# design.net
KiCad netlist of a schematic drawn in EasyEDA Pro
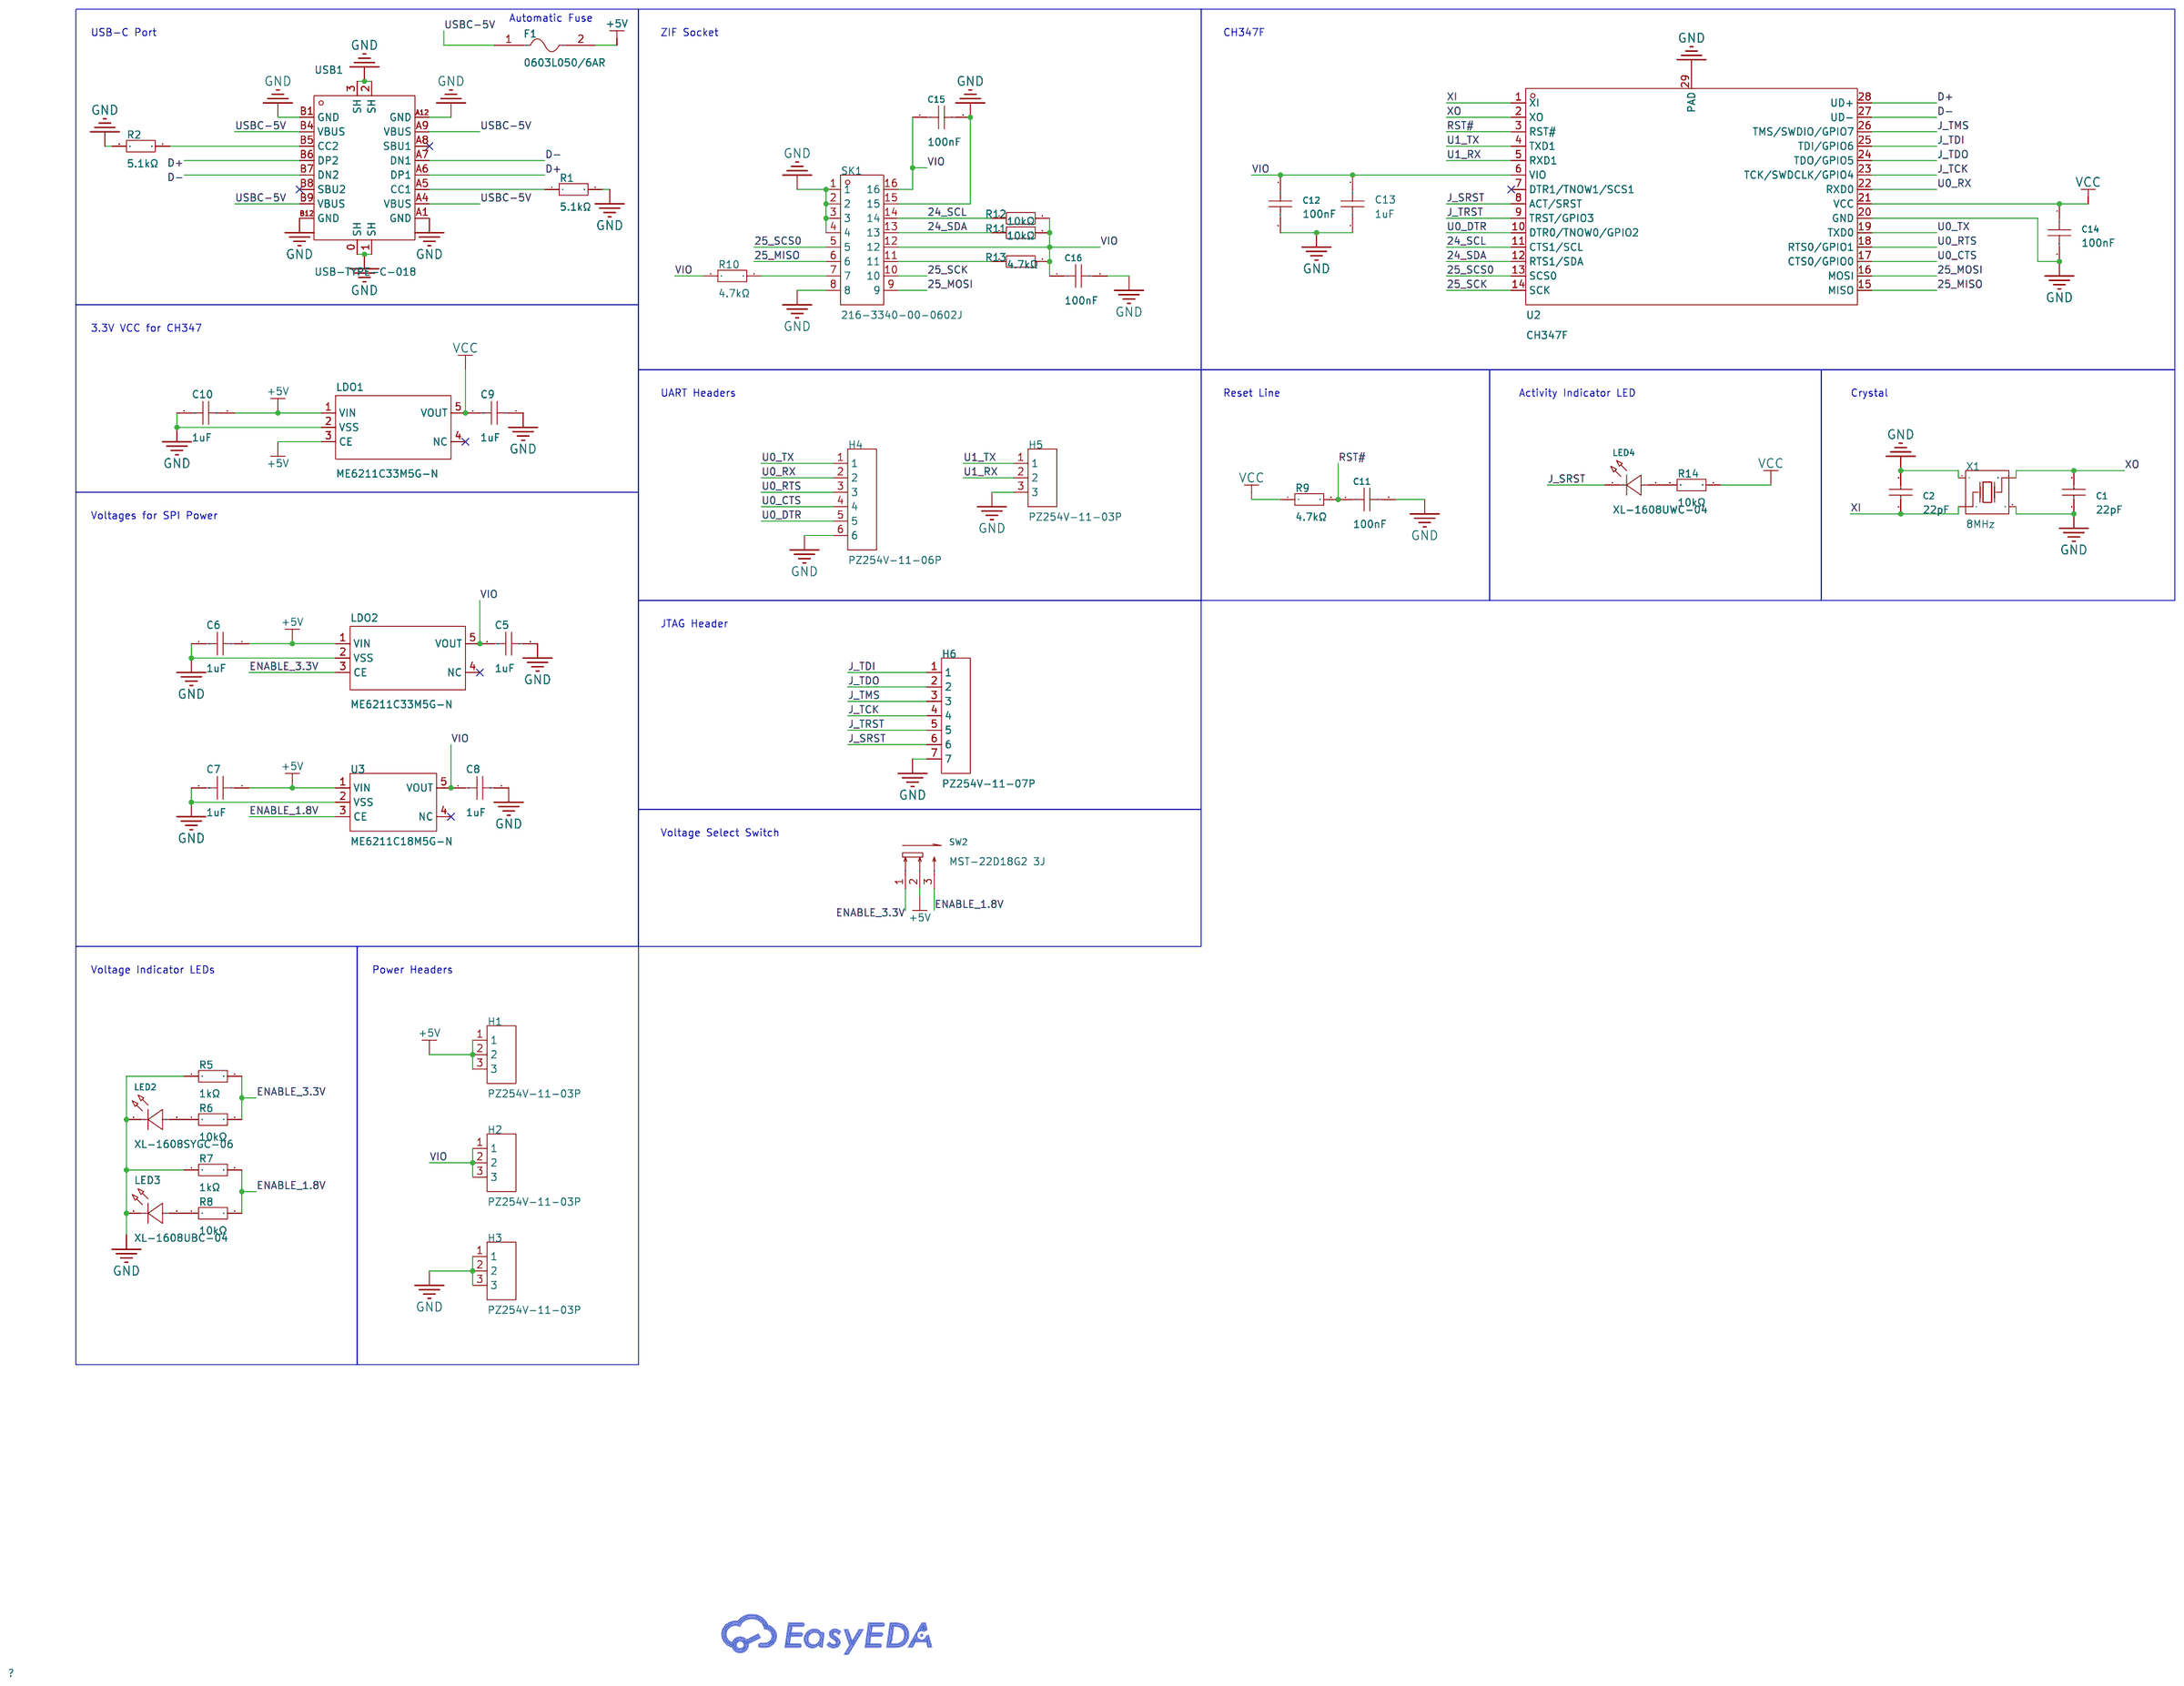
[diagram p0: schematic sheet]

(export (version "E")
  (design (tool "Eeschema 10.0.6"))
  (components
    (comp (ref "C1")
      (value "22pF")
      (footprint "easyedapro:C0402")
      (fields
        (field (name "Manufacturer Part") "CC0402JRNPO9BN220")
        (field (name "Manufacturer") "YAGEO(国巨)")
      )
      (libsource (lib "easyedapro") (part "CC0402JRNPO9BN220"))
    )
    (comp (ref "C2")
      (value "22pF")
      (footprint "easyedapro:C0402")
      (fields
        (field (name "Manufacturer Part") "CC0402JRNPO9BN220")
        (field (name "Manufacturer") "YAGEO(国巨)")
      )
      (libsource (lib "easyedapro") (part "CC0402JRNPO9BN220"))
    )
    (comp (ref "C5")
      (value "1uF")
      (footprint "easyedapro:C0603")
      (fields
        (field (name "Manufacturer Part") "CL10A105KB8NNNC")
        (field (name "Manufacturer") "SAMSUNG(三星)")
      )
      (libsource (lib "easyedapro") (part "CL10A105KB8NNNC"))
    )
    (comp (ref "C6")
      (value "1uF")
      (footprint "easyedapro:C0603")
      (fields
        (field (name "Manufacturer Part") "CL10A105KB8NNNC")
        (field (name "Manufacturer") "SAMSUNG(三星)")
      )
      (libsource (lib "easyedapro") (part "CL10A105KB8NNNC"))
    )
    (comp (ref "C7")
      (value "1uF")
      (footprint "easyedapro:C0603")
      (fields
        (field (name "Manufacturer Part") "CL10A105KB8NNNC")
        (field (name "Manufacturer") "SAMSUNG(三星)")
      )
      (libsource (lib "easyedapro") (part "CL10A105KB8NNNC"))
    )
    (comp (ref "C8")
      (value "1uF")
      (footprint "easyedapro:C0603")
      (fields
        (field (name "Manufacturer Part") "CL10A105KB8NNNC")
        (field (name "Manufacturer") "SAMSUNG(三星)")
      )
      (libsource (lib "easyedapro") (part "CL10A105KB8NNNC"))
    )
    (comp (ref "C9")
      (value "1uF")
      (footprint "easyedapro:C0603")
      (fields
        (field (name "Manufacturer Part") "CL10A105KB8NNNC")
        (field (name "Manufacturer") "SAMSUNG(三星)")
      )
      (libsource (lib "easyedapro") (part "CL10A105KB8NNNC"))
    )
    (comp (ref "C10")
      (value "1uF")
      (footprint "easyedapro:C0603")
      (fields
        (field (name "Manufacturer Part") "CL10A105KB8NNNC")
        (field (name "Manufacturer") "SAMSUNG(三星)")
      )
      (libsource (lib "easyedapro") (part "CL10A105KB8NNNC"))
    )
    (comp (ref "C11")
      (value "100nF")
      (footprint "easyedapro:C0603")
      (fields
        (field (name "Manufacturer Part") "CL10B104KB8NNNC")
        (field (name "Manufacturer") "SAMSUNG(三星)")
      )
      (libsource (lib "easyedapro") (part "CL10B104KB8NNNC"))
    )
    (comp (ref "C12")
      (value "100nF")
      (footprint "easyedapro:C0603")
      (fields
        (field (name "Manufacturer Part") "CL10B104KB8NNNC")
        (field (name "Manufacturer") "SAMSUNG(三星)")
      )
      (libsource (lib "easyedapro") (part "CL10B104KB8NNNC"))
    )
    (comp (ref "C13")
      (value "1uF")
      (footprint "easyedapro:C0603")
      (fields
        (field (name "Manufacturer Part") "CL10A105KB8NNNC")
        (field (name "Manufacturer") "SAMSUNG(三星)")
      )
      (libsource (lib "easyedapro") (part "CL10A105KB8NNNC"))
    )
    (comp (ref "C14")
      (value "100nF")
      (footprint "easyedapro:C0603")
      (fields
        (field (name "Manufacturer Part") "CL10B104KB8NNNC")
        (field (name "Manufacturer") "SAMSUNG(三星)")
      )
      (libsource (lib "easyedapro") (part "CL10B104KB8NNNC"))
    )
    (comp (ref "C15")
      (value "100nF")
      (footprint "easyedapro:C0603")
      (fields
        (field (name "Manufacturer Part") "CL10B104KB8NNNC")
        (field (name "Manufacturer") "SAMSUNG(三星)")
      )
      (libsource (lib "easyedapro") (part "CL10B104KB8NNNC"))
    )
    (comp (ref "C16")
      (value "100nF")
      (footprint "easyedapro:C0603")
      (fields
        (field (name "Manufacturer Part") "CL10B104KB8NNNC")
        (field (name "Manufacturer") "SAMSUNG(三星)")
      )
      (libsource (lib "easyedapro") (part "CL10B104KB8NNNC"))
    )
    (comp (ref "F1")
      (value "0603L050/6AR")
      (footprint "easyedapro:F0603")
      (fields (field (name "Manufacturer") "LUTE(陆特)"))
      (libsource (lib "easyedapro") (part "0603L050/6AR"))
    )
    (comp (ref "H1")
      (value "PZ254V-11-03P")
      (footprint "easyedapro:HDR-TH_3P-P2.54-V-M")
      (fields (field (name "Manufacturer") "XFCN(兴飞)"))
      (libsource (lib "easyedapro") (part "PZ254V-11-03P_C2937625"))
    )
    (comp (ref "H2")
      (value "PZ254V-11-03P")
      (footprint "easyedapro:HDR-TH_3P-P2.54-V-M")
      (fields (field (name "Manufacturer") "XFCN(兴飞)"))
      (libsource (lib "easyedapro") (part "PZ254V-11-03P_C2937625"))
    )
    (comp (ref "H3")
      (value "PZ254V-11-03P")
      (footprint "easyedapro:HDR-TH_3P-P2.54-V-M")
      (fields (field (name "Manufacturer") "XFCN(兴飞)"))
      (libsource (lib "easyedapro") (part "PZ254V-11-03P_C2937625"))
    )
    (comp (ref "H4")
      (value "PZ254V-11-06P")
      (footprint "easyedapro:HDR-TH_6P-P2.54-V-M")
      (fields (field (name "Manufacturer") "XFCN(兴飞)"))
      (libsource (lib "easyedapro") (part "PZ254V-11-06P"))
    )
    (comp (ref "H5")
      (value "PZ254V-11-03P")
      (footprint "easyedapro:HDR-TH_3P-P2.54-V-M")
      (fields (field (name "Manufacturer") "XFCN(兴飞)"))
      (libsource (lib "easyedapro") (part "PZ254V-11-03P_C2937625"))
    )
    (comp (ref "H6")
      (value "PZ254V-11-07P")
      (footprint "easyedapro:HDR-TH_7P-P2.54-V-M")
      (fields (field (name "Manufacturer") "XFCN(兴飞)"))
      (libsource (lib "easyedapro") (part "PZ254V-11-07P"))
    )
    (comp (ref "LDO1")
      (value "ME6211C33M5G-N")
      (footprint "easyedapro:SOT-23-5_L3.0-W1.7-P0.95-LS2.8-BL")
      (fields (field (name "Manufacturer") "MICRONE(南京微盟)"))
      (libsource (lib "easyedapro") (part "ME6211C33M5G-N"))
    )
    (comp (ref "LDO2")
      (value "ME6211C33M5G-N")
      (footprint "easyedapro:SOT-23-5_L3.0-W1.7-P0.95-LS2.8-BL")
      (fields (field (name "Manufacturer") "MICRONE(南京微盟)"))
      (libsource (lib "easyedapro") (part "ME6211C33M5G-N"))
    )
    (comp (ref "LED2")
      (value "XL-1608SYGC-06")
      (footprint "easyedapro:LED0603-RD_GREEN")
      (fields (field (name "Manufacturer") "XINGLIGHT(成兴光)"))
      (libsource (lib "easyedapro") (part "XL-1608SYGC-06"))
    )
    (comp (ref "LED3")
      (value "XL-1608UBC-04")
      (footprint "easyedapro:LED0603-RD_BLUE")
      (fields (field (name "Manufacturer") "XINGLIGHT(成兴光)"))
      (libsource (lib "easyedapro") (part "XL-1608UBC-04"))
    )
    (comp (ref "LED4")
      (value "XL-1608UWC-04")
      (footprint "easyedapro:LED0603-RD_WHITE")
      (fields (field (name "Manufacturer") "XINGLIGHT(成兴光)"))
      (libsource (lib "easyedapro") (part "XL-1608UWC-04"))
    )
    (comp (ref "R1")
      (value "5.1kΩ")
      (footprint "easyedapro:R0603")
      (fields (field (name "Manufacturer Part") "RC0603FR-075K1L") (field (name "Manufacturer") "YAGEO(国巨)"))
      (libsource (lib "easyedapro") (part "RC0603FR-075K1L"))
    )
    (comp (ref "R2")
      (value "5.1kΩ")
      (footprint "easyedapro:R0603")
      (fields (field (name "Manufacturer Part") "RC0603FR-075K1L") (field (name "Manufacturer") "YAGEO(国巨)"))
      (libsource (lib "easyedapro") (part "RC0603FR-075K1L"))
    )
    (comp (ref "R5")
      (value "1kΩ")
      (footprint "easyedapro:R0603")
      (fields (field (name "Manufacturer Part") "RC0603FR-071KL") (field (name "Manufacturer") "YAGEO(国巨)"))
      (libsource (lib "easyedapro") (part "RC0603FR-071KL"))
    )
    (comp (ref "R6")
      (value "10kΩ")
      (footprint "easyedapro:R0603")
      (fields (field (name "Manufacturer Part") "RC0603FR-0710KL") (field (name "Manufacturer") "YAGEO(国巨)"))
      (libsource (lib "easyedapro") (part "RC0603FR-0710KL"))
    )
    (comp (ref "R7")
      (value "1kΩ")
      (footprint "easyedapro:R0603")
      (fields (field (name "Manufacturer Part") "RC0603FR-071KL") (field (name "Manufacturer") "YAGEO(国巨)"))
      (libsource (lib "easyedapro") (part "RC0603FR-071KL"))
    )
    (comp (ref "R8")
      (value "10kΩ")
      (footprint "easyedapro:R0603")
      (fields (field (name "Manufacturer Part") "RC0603FR-0710KL") (field (name "Manufacturer") "YAGEO(国巨)"))
      (libsource (lib "easyedapro") (part "RC0603FR-0710KL"))
    )
    (comp (ref "R9")
      (value "4.7kΩ")
      (footprint "easyedapro:R0603")
      (fields (field (name "Manufacturer Part") "RC0603FR-074K7L") (field (name "Manufacturer") "YAGEO(国巨)"))
      (libsource (lib "easyedapro") (part "RC0603FR-074K7L"))
    )
    (comp (ref "R10")
      (value "4.7kΩ")
      (footprint "easyedapro:R0603")
      (fields (field (name "Manufacturer Part") "RC0603FR-074K7L") (field (name "Manufacturer") "YAGEO(国巨)"))
      (libsource (lib "easyedapro") (part "RC0603FR-074K7L"))
    )
    (comp (ref "R11")
      (value "10kΩ")
      (footprint "easyedapro:R0603")
      (fields (field (name "Manufacturer Part") "RC0603FR-0710KL") (field (name "Manufacturer") "YAGEO(国巨)"))
      (libsource (lib "easyedapro") (part "RC0603FR-0710KL"))
    )
    (comp (ref "R12")
      (value "10kΩ")
      (footprint "easyedapro:R0603")
      (fields (field (name "Manufacturer Part") "RC0603FR-0710KL") (field (name "Manufacturer") "YAGEO(国巨)"))
      (libsource (lib "easyedapro") (part "RC0603FR-0710KL"))
    )
    (comp (ref "R13")
      (value "4.7kΩ")
      (footprint "easyedapro:R0603")
      (fields (field (name "Manufacturer Part") "RC0603FR-074K7L") (field (name "Manufacturer") "YAGEO(国巨)"))
      (libsource (lib "easyedapro") (part "RC0603FR-074K7L"))
    )
    (comp (ref "R14")
      (value "10kΩ")
      (footprint "easyedapro:R0603")
      (fields (field (name "Manufacturer Part") "RC0603FR-0710KL") (field (name "Manufacturer") "YAGEO(国巨)"))
      (libsource (lib "easyedapro") (part "RC0603FR-0710KL"))
    )
    (comp (ref "SK1")
      (value "216-3340-00-0602J")
      (footprint "easyedapro:DIP-16_216-3340-00-0602J")
      (fields (field (name "Manufacturer") "3M"))
      (libsource (lib "easyedapro") (part "216-3340-00-0602J"))
    )
    (comp (ref "SW2")
      (value "MST-22D18G2 3J")
      (footprint "easyedapro:SW-SMD_SHOUHAN_MST-22D18G23J_C2875122")
      (fields (field (name "Manufacturer") "SHOU HAN(首韩)"))
      (libsource (lib "easyedapro") (part "MST-22D18G2 3J_C2875122"))
    )
    (comp (ref "U2")
      (value "CH347F")
      (footprint "easyedapro:QFN-28_L4.0-W4.0-P0.40-BL-EP2.7")
      (fields (field (name "Manufacturer") "WCH(南京沁恒)"))
      (libsource (lib "easyedapro") (part "CH347F"))
    )
    (comp (ref "U3")
      (value "ME6211C18M5G-N")
      (footprint "easyedapro:SOT-23-5_L3.0-W1.7-P0.95-LS2.8-BR")
      (fields (field (name "Manufacturer") "MICRONE(南京微盟)"))
      (libsource (lib "easyedapro") (part "ME6211C18M5G-N"))
    )
    (comp (ref "USB1")
      (value "USB-TYPE-C-018")
      (footprint "easyedapro:USB-C_SMD-TYPE-C-31-M-12")
      (fields (field (name "Manufacturer") "DEALON(德艺隆)"))
      (libsource (lib "easyedapro") (part "USB-TYPE-C-018"))
    )
    (comp (ref "X1")
      (value "8MHz")
      (footprint "easyedapro:CRYSTAL-SMD_4P-L3.2-W2.5-BL")
      (fields (field (name "Manufacturer Part") "TAXM8M4RDBCCT2T") (field (name "Manufacturer") "YJX(雅晶鑫)"))
      (libsource (lib "easyedapro") (part "TAXM8M4RDBCCT2T"))
    )
  )
  (nets
    (net (code "1") (name "+5V") (class "Default")
      (node (ref "C10") (pin "1") (pinfunction "1_1") (pintype "unspecified"))
      (node (ref "C6") (pin "1") (pinfunction "1_1") (pintype "unspecified"))
      (node (ref "C7") (pin "1") (pinfunction "1_1") (pintype "unspecified"))
      (node (ref "F1") (pin "2") (pinfunction "2_2") (pintype "unspecified"))
      (node (ref "H1") (pin "1") (pinfunction "1_1") (pintype "unspecified"))
      (node (ref "H1") (pin "2") (pinfunction "2_2") (pintype "unspecified"))
      (node (ref "H1") (pin "3") (pinfunction "3_3") (pintype "unspecified"))
      (node (ref "LDO1") (pin "1") (pinfunction "VIN_1") (pintype "unspecified"))
      (node (ref "LDO1") (pin "3") (pinfunction "CE_3") (pintype "unspecified"))
      (node (ref "LDO2") (pin "1") (pinfunction "VIN_1") (pintype "unspecified"))
      (node (ref "SW2") (pin "2") (pinfunction "2_2") (pintype "input"))
      (node (ref "U3") (pin "1") (pinfunction "VIN_1") (pintype "unspecified"))
    )
    (net (code "2") (name "/24_SCL") (class "Default")
      (node (ref "R12") (pin "1") (pinfunction "1_1") (pintype "input"))
      (node (ref "SK1") (pin "14") (pinfunction "14_14") (pintype "unspecified"))
      (node (ref "U2") (pin "11") (pinfunction "CTS1/SCL_11") (pintype "unspecified"))
    )
    (net (code "3") (name "/24_SDA") (class "Default")
      (node (ref "R11") (pin "1") (pinfunction "1_1") (pintype "input"))
      (node (ref "SK1") (pin "13") (pinfunction "13_13") (pintype "unspecified"))
      (node (ref "U2") (pin "12") (pinfunction "RTS1/SDA_12") (pintype "unspecified"))
    )
    (net (code "4") (name "/25_MISO") (class "Default")
      (node (ref "SK1") (pin "6") (pinfunction "6_6") (pintype "unspecified"))
      (node (ref "U2") (pin "15") (pinfunction "MISO_15") (pintype "unspecified"))
    )
    (net (code "5") (name "/25_MOSI") (class "Default")
      (node (ref "SK1") (pin "9") (pinfunction "9_9") (pintype "unspecified"))
      (node (ref "U2") (pin "16") (pinfunction "MOSI_16") (pintype "unspecified"))
    )
    (net (code "6") (name "/25_SCK") (class "Default")
      (node (ref "SK1") (pin "10") (pinfunction "10_10") (pintype "unspecified"))
      (node (ref "U2") (pin "14") (pinfunction "SCK_14") (pintype "unspecified"))
    )
    (net (code "7") (name "/25_SCS0") (class "Default")
      (node (ref "SK1") (pin "5") (pinfunction "5_5") (pintype "unspecified"))
      (node (ref "U2") (pin "13") (pinfunction "SCS0_13") (pintype "unspecified"))
    )
    (net (code "8") (name "/D+") (class "Default")
      (node (ref "U2") (pin "28") (pinfunction "UD+_28") (pintype "unspecified"))
      (node (ref "USB1") (pin "A6") (pinfunction "DP1_A6") (pintype "unspecified"))
      (node (ref "USB1") (pin "B6") (pinfunction "DP2_B6") (pintype "unspecified"))
    )
    (net (code "9") (name "/D-") (class "Default")
      (node (ref "U2") (pin "27") (pinfunction "UD-_27") (pintype "unspecified"))
      (node (ref "USB1") (pin "A7") (pinfunction "DN1_A7") (pintype "unspecified"))
      (node (ref "USB1") (pin "B7") (pinfunction "DN2_B7") (pintype "unspecified"))
    )
    (net (code "10") (name "/ENABLE_1.8V") (class "Default")
      (node (ref "R7") (pin "2") (pinfunction "2_2") (pintype "input"))
      (node (ref "R8") (pin "2") (pinfunction "2_2") (pintype "input"))
      (node (ref "SW2") (pin "3") (pinfunction "3_3") (pintype "input"))
      (node (ref "U3") (pin "3") (pinfunction "CE_3") (pintype "unspecified"))
    )
    (net (code "11") (name "/ENABLE_3.3V") (class "Default")
      (node (ref "LDO2") (pin "3") (pinfunction "CE_3") (pintype "unspecified"))
      (node (ref "R5") (pin "2") (pinfunction "2_2") (pintype "input"))
      (node (ref "R6") (pin "2") (pinfunction "2_2") (pintype "input"))
      (node (ref "SW2") (pin "1") (pinfunction "1_1") (pintype "input"))
    )
    (net (code "12") (name "/J_SRST") (class "Default")
      (node (ref "H6") (pin "6") (pinfunction "6_6") (pintype "unspecified"))
      (node (ref "LED4") (pin "1") (pinfunction "K_1") (pintype "input"))
      (node (ref "U2") (pin "8") (pinfunction "ACT/SRST_8") (pintype "unspecified"))
    )
    (net (code "13") (name "/J_TCK") (class "Default")
      (node (ref "H6") (pin "4") (pinfunction "4_4") (pintype "unspecified"))
      (node (ref "U2") (pin "23") (pinfunction "TCK/SWDCLK/GPIO4_23") (pintype "unspecified"))
    )
    (net (code "14") (name "/J_TDI") (class "Default")
      (node (ref "H6") (pin "1") (pinfunction "1_1") (pintype "unspecified"))
      (node (ref "U2") (pin "25") (pinfunction "TDI/GPIO6_25") (pintype "unspecified"))
    )
    (net (code "15") (name "/J_TDO") (class "Default")
      (node (ref "H6") (pin "2") (pinfunction "2_2") (pintype "unspecified"))
      (node (ref "U2") (pin "24") (pinfunction "TDO/GPIO5_24") (pintype "unspecified"))
    )
    (net (code "16") (name "/J_TMS") (class "Default")
      (node (ref "H6") (pin "3") (pinfunction "3_3") (pintype "unspecified"))
      (node (ref "U2") (pin "26") (pinfunction "TMS/SWDIO/GPIO7_26") (pintype "unspecified"))
    )
    (net (code "17") (name "/J_TRST") (class "Default")
      (node (ref "H6") (pin "5") (pinfunction "5_5") (pintype "unspecified"))
      (node (ref "U2") (pin "9") (pinfunction "TRST/GPIO3_9") (pintype "unspecified"))
    )
    (net (code "18") (name "/RST#") (class "Default")
      (node (ref "C11") (pin "1") (pinfunction "1_1") (pintype "input"))
      (node (ref "R9") (pin "2") (pinfunction "2_2") (pintype "input"))
      (node (ref "U2") (pin "3") (pinfunction "RST#_3") (pintype "unspecified"))
    )
    (net (code "19") (name "/U0_CTS") (class "Default")
      (node (ref "H4") (pin "4") (pinfunction "4_4") (pintype "unspecified"))
      (node (ref "U2") (pin "17") (pinfunction "CTS0/GPIO0_17") (pintype "unspecified"))
    )
    (net (code "20") (name "/U0_DTR") (class "Default")
      (node (ref "H4") (pin "5") (pinfunction "5_5") (pintype "unspecified"))
      (node (ref "U2") (pin "10") (pinfunction "DTR0/TNOW0/GPIO2_10") (pintype "unspecified"))
    )
    (net (code "21") (name "/U0_RTS") (class "Default")
      (node (ref "H4") (pin "3") (pinfunction "3_3") (pintype "unspecified"))
      (node (ref "U2") (pin "18") (pinfunction "RTS0/GPIO1_18") (pintype "unspecified"))
    )
    (net (code "22") (name "/U0_RX") (class "Default")
      (node (ref "H4") (pin "2") (pinfunction "2_2") (pintype "unspecified"))
      (node (ref "U2") (pin "22") (pinfunction "RXD0_22") (pintype "unspecified"))
    )
    (net (code "23") (name "/U0_TX") (class "Default")
      (node (ref "H4") (pin "1") (pinfunction "1_1") (pintype "unspecified"))
      (node (ref "U2") (pin "19") (pinfunction "TXD0_19") (pintype "unspecified"))
    )
    (net (code "24") (name "/U1_RX") (class "Default")
      (node (ref "H5") (pin "2") (pinfunction "2_2") (pintype "unspecified"))
      (node (ref "U2") (pin "5") (pinfunction "RXD1_5") (pintype "unspecified"))
    )
    (net (code "25") (name "/U1_TX") (class "Default")
      (node (ref "H5") (pin "1") (pinfunction "1_1") (pintype "unspecified"))
      (node (ref "U2") (pin "4") (pinfunction "TXD1_4") (pintype "unspecified"))
    )
    (net (code "26") (name "/USBC-5V") (class "Default")
      (node (ref "F1") (pin "1") (pinfunction "1_1") (pintype "unspecified"))
      (node (ref "USB1") (pin "A4") (pinfunction "VBUS_A4") (pintype "unspecified"))
      (node (ref "USB1") (pin "A9") (pinfunction "VBUS_A9") (pintype "unspecified"))
      (node (ref "USB1") (pin "B4") (pinfunction "VBUS_B4") (pintype "unspecified"))
      (node (ref "USB1") (pin "B9") (pinfunction "VBUS_B9") (pintype "unspecified"))
    )
    (net (code "27") (name "/VIO") (class "Default")
      (node (ref "C12") (pin "1") (pinfunction "1_1") (pintype "input"))
      (node (ref "C13") (pin "1") (pinfunction "1_1") (pintype "unspecified"))
      (node (ref "C15") (pin "1") (pinfunction "1_1") (pintype "input"))
      (node (ref "C16") (pin "1") (pinfunction "1_1") (pintype "input"))
      (node (ref "C5") (pin "2") (pinfunction "2_2") (pintype "unspecified"))
      (node (ref "C8") (pin "2") (pinfunction "2_2") (pintype "unspecified"))
      (node (ref "H2") (pin "1") (pinfunction "1_1") (pintype "unspecified"))
      (node (ref "H2") (pin "2") (pinfunction "2_2") (pintype "unspecified"))
      (node (ref "H2") (pin "3") (pinfunction "3_3") (pintype "unspecified"))
      (node (ref "LDO2") (pin "5") (pinfunction "VOUT_5") (pintype "unspecified"))
      (node (ref "R10") (pin "1") (pinfunction "1_1") (pintype "input"))
      (node (ref "R11") (pin "2") (pinfunction "2_2") (pintype "input"))
      (node (ref "R12") (pin "2") (pinfunction "2_2") (pintype "input"))
      (node (ref "R13") (pin "2") (pinfunction "2_2") (pintype "input"))
      (node (ref "SK1") (pin "12") (pinfunction "12_12") (pintype "unspecified"))
      (node (ref "SK1") (pin "16") (pinfunction "16_16") (pintype "unspecified"))
      (node (ref "U2") (pin "6") (pinfunction "VIO_6") (pintype "unspecified"))
      (node (ref "U3") (pin "5") (pinfunction "VOUT_5") (pintype "unspecified"))
    )
    (net (code "28") (name "/XI") (class "Default")
      (node (ref "C2") (pin "1") (pinfunction "1_1") (pintype "input"))
      (node (ref "U2") (pin "1") (pinfunction "XI_1") (pintype "unspecified"))
      (node (ref "X1") (pin "1") (pinfunction "1_1") (pintype "input"))
    )
    (net (code "29") (name "/XO") (class "Default")
      (node (ref "C1") (pin "2") (pinfunction "2_2") (pintype "input"))
      (node (ref "U2") (pin "2") (pinfunction "XO_2") (pintype "unspecified"))
      (node (ref "X1") (pin "3") (pinfunction "3_3") (pintype "input"))
    )
    (net (code "30") (name "GND") (class "Default")
      (node (ref "C1") (pin "1") (pinfunction "1_1") (pintype "input"))
      (node (ref "C10") (pin "2") (pinfunction "2_2") (pintype "unspecified"))
      (node (ref "C11") (pin "2") (pinfunction "2_2") (pintype "input"))
      (node (ref "C12") (pin "2") (pinfunction "2_2") (pintype "input"))
      (node (ref "C13") (pin "2") (pinfunction "2_2") (pintype "unspecified"))
      (node (ref "C14") (pin "2") (pinfunction "2_2") (pintype "input"))
      (node (ref "C15") (pin "2") (pinfunction "2_2") (pintype "input"))
      (node (ref "C16") (pin "2") (pinfunction "2_2") (pintype "input"))
      (node (ref "C2") (pin "2") (pinfunction "2_2") (pintype "input"))
      (node (ref "C5") (pin "1") (pinfunction "1_1") (pintype "unspecified"))
      (node (ref "C6") (pin "2") (pinfunction "2_2") (pintype "unspecified"))
      (node (ref "C7") (pin "2") (pinfunction "2_2") (pintype "unspecified"))
      (node (ref "C8") (pin "1") (pinfunction "1_1") (pintype "unspecified"))
      (node (ref "C9") (pin "1") (pinfunction "1_1") (pintype "unspecified"))
      (node (ref "H3") (pin "1") (pinfunction "1_1") (pintype "unspecified"))
      (node (ref "H3") (pin "2") (pinfunction "2_2") (pintype "unspecified"))
      (node (ref "H3") (pin "3") (pinfunction "3_3") (pintype "unspecified"))
      (node (ref "H4") (pin "6") (pinfunction "6_6") (pintype "unspecified"))
      (node (ref "H5") (pin "3") (pinfunction "3_3") (pintype "unspecified"))
      (node (ref "H6") (pin "7") (pinfunction "7_7") (pintype "unspecified"))
      (node (ref "LDO1") (pin "2") (pinfunction "VSS_2") (pintype "unspecified"))
      (node (ref "LDO2") (pin "2") (pinfunction "VSS_2") (pintype "unspecified"))
      (node (ref "LED2") (pin "1") (pinfunction "K_1") (pintype "input"))
      (node (ref "LED3") (pin "1") (pinfunction "K_1") (pintype "unspecified"))
      (node (ref "R1") (pin "2") (pinfunction "2_2") (pintype "input"))
      (node (ref "R2") (pin "1") (pinfunction "1_1") (pintype "input"))
      (node (ref "R5") (pin "1") (pinfunction "1_1") (pintype "input"))
      (node (ref "R7") (pin "1") (pinfunction "1_1") (pintype "input"))
      (node (ref "SK1") (pin "1") (pinfunction "1_1") (pintype "unspecified"))
      (node (ref "SK1") (pin "15") (pinfunction "15_15") (pintype "unspecified"))
      (node (ref "SK1") (pin "2") (pinfunction "2_2") (pintype "unspecified"))
      (node (ref "SK1") (pin "3") (pinfunction "3_3") (pintype "unspecified"))
      (node (ref "SK1") (pin "4") (pinfunction "4_4") (pintype "unspecified"))
      (node (ref "SK1") (pin "8") (pinfunction "8_8") (pintype "unspecified"))
      (node (ref "U2") (pin "20") (pinfunction "GND_20") (pintype "unspecified"))
      (node (ref "U2") (pin "29") (pinfunction "PAD_29") (pintype "unspecified"))
      (node (ref "U3") (pin "2") (pinfunction "VSS_2") (pintype "unspecified"))
      (node (ref "USB1") (pin "0") (pinfunction "SH_0") (pintype "unspecified"))
      (node (ref "USB1") (pin "1") (pinfunction "SH_1") (pintype "unspecified"))
      (node (ref "USB1") (pin "2") (pinfunction "SH_2") (pintype "unspecified"))
      (node (ref "USB1") (pin "3") (pinfunction "SH_3") (pintype "unspecified"))
      (node (ref "USB1") (pin "A1") (pinfunction "GND_A1") (pintype "unspecified"))
      (node (ref "USB1") (pin "A12") (pinfunction "GND_A12") (pintype "unspecified"))
      (node (ref "USB1") (pin "B1") (pinfunction "GND_B1") (pintype "unspecified"))
      (node (ref "USB1") (pin "B12") (pinfunction "GND_B12") (pintype "unspecified"))
      (node (ref "X1") (pin "2") (pinfunction "2_2") (pintype "input"))
      (node (ref "X1") (pin "4") (pinfunction "4_4") (pintype "input"))
    )
    (net (code "31") (name "Net-(LED2-A)") (class "Default")
      (node (ref "LED2") (pin "2") (pinfunction "A_2") (pintype "input"))
      (node (ref "R6") (pin "1") (pinfunction "1_1") (pintype "input"))
    )
    (net (code "32") (name "Net-(LED3-A)") (class "Default")
      (node (ref "LED3") (pin "2") (pinfunction "A_2") (pintype "unspecified"))
      (node (ref "R8") (pin "1") (pinfunction "1_1") (pintype "input"))
    )
    (net (code "33") (name "Net-(LED4-A)") (class "Default")
      (node (ref "LED4") (pin "2") (pinfunction "A_2") (pintype "input"))
      (node (ref "R14") (pin "1") (pinfunction "1_1") (pintype "input"))
    )
    (net (code "34") (name "Net-(R10-Pad2)") (class "Default")
      (node (ref "R10") (pin "2") (pinfunction "2_2") (pintype "input"))
      (node (ref "SK1") (pin "7") (pinfunction "7_7") (pintype "unspecified"))
    )
    (net (code "35") (name "Net-(R13-Pad1)") (class "Default")
      (node (ref "R13") (pin "1") (pinfunction "1_1") (pintype "input"))
      (node (ref "SK1") (pin "11") (pinfunction "11_11") (pintype "unspecified"))
    )
    (net (code "36") (name "Net-(USB1-CC1)") (class "Default")
      (node (ref "R1") (pin "1") (pinfunction "1_1") (pintype "input"))
      (node (ref "USB1") (pin "A5") (pinfunction "CC1_A5") (pintype "unspecified"))
    )
    (net (code "37") (name "Net-(USB1-CC2)") (class "Default")
      (node (ref "R2") (pin "2") (pinfunction "2_2") (pintype "input"))
      (node (ref "USB1") (pin "B5") (pinfunction "CC2_B5") (pintype "unspecified"))
    )
    (net (code "38") (name "VCC") (class "Default")
      (node (ref "C14") (pin "1") (pinfunction "1_1") (pintype "input"))
      (node (ref "C9") (pin "2") (pinfunction "2_2") (pintype "unspecified"))
      (node (ref "LDO1") (pin "5") (pinfunction "VOUT_5") (pintype "unspecified"))
      (node (ref "R14") (pin "2") (pinfunction "2_2") (pintype "input"))
      (node (ref "R9") (pin "1") (pinfunction "1_1") (pintype "input"))
      (node (ref "U2") (pin "21") (pinfunction "VCC_21") (pintype "unspecified"))
    )
    (net (code "39") (name "unconnected-(LDO1-NC-Pad4)") (class "Default")
      (node (ref "LDO1") (pin "4") (pinfunction "NC_4") (pintype "unspecified+no_connect"))
    )
    (net (code "40") (name "unconnected-(LDO2-NC-Pad4)") (class "Default")
      (node (ref "LDO2") (pin "4") (pinfunction "NC_4") (pintype "unspecified+no_connect"))
    )
    (net (code "41") (name "unconnected-(U2-DTR1{slash}TNOW1{slash}SCS1-Pad7)") (class "Default")
      (node (ref "U2") (pin "7") (pinfunction "DTR1/TNOW1/SCS1_7") (pintype "unspecified+no_connect"))
    )
    (net (code "42") (name "unconnected-(U3-NC-Pad4)") (class "Default")
      (node (ref "U3") (pin "4") (pinfunction "NC_4") (pintype "unspecified+no_connect"))
    )
    (net (code "43") (name "unconnected-(USB1-SBU1-PadA8)") (class "Default")
      (node (ref "USB1") (pin "A8") (pinfunction "SBU1_A8") (pintype "unspecified+no_connect"))
    )
    (net (code "44") (name "unconnected-(USB1-SBU2-PadB8)") (class "Default")
      (node (ref "USB1") (pin "B8") (pinfunction "SBU2_B8") (pintype "unspecified+no_connect"))
    )
  )
)
